# X-Track_Power.net
KiCad netlist of a schematic drawn in Altium Designer
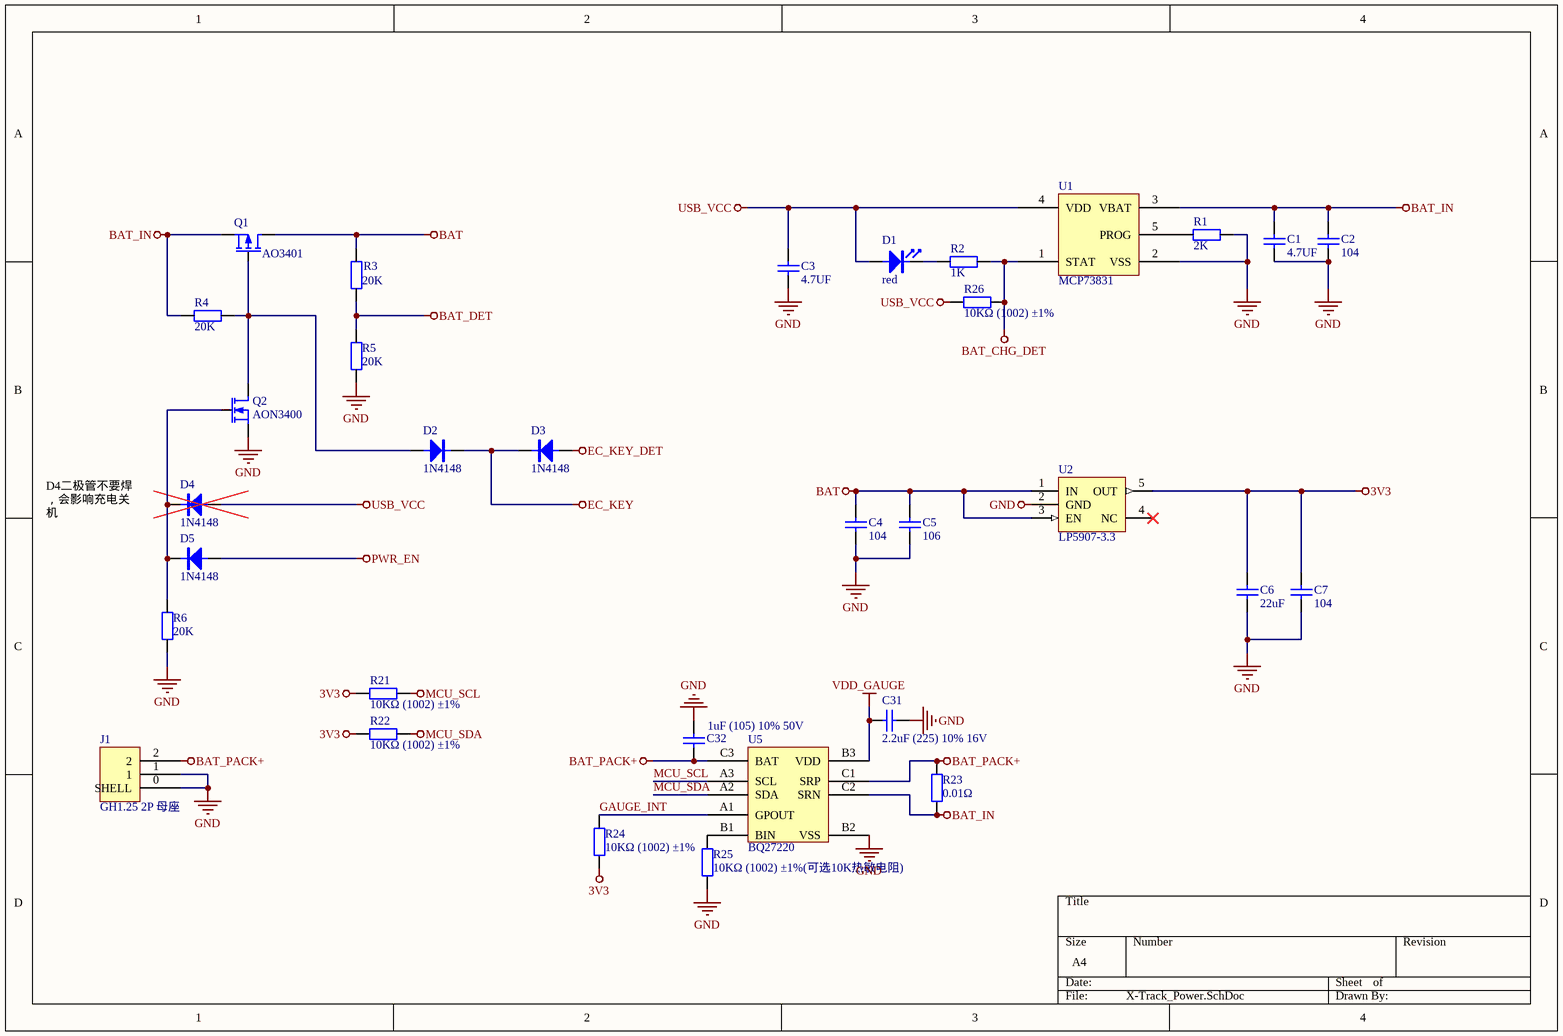
[diagram p0: X-Track_Power.SchDoc]

(export (version "E")
  (design (tool "Eeschema 10.0.6"))
  (components
    (comp (ref "C1")
      (value "4.7UF")
      (footprint "电容_C0805")
      (fields (field (name "C") "4.7UF"))
      (libsource (lib "元件库") (part "cap"))
    )
    (comp (ref "C2")
      (value "104")
      (footprint "电容_C0603")
      (fields (field (name "C") "104"))
      (libsource (lib "元件库") (part "cap"))
    )
    (comp (ref "C3")
      (value "4.7UF")
      (footprint "电容_C0805")
      (fields (field (name "C") "4.7UF"))
      (libsource (lib "元件库") (part "cap"))
    )
    (comp (ref "C4")
      (value "104")
      (footprint "电容_C0603")
      (fields (field (name "C") "104"))
      (libsource (lib "元件库") (part "cap"))
    )
    (comp (ref "C5")
      (value "106")
      (footprint "电容_C0603")
      (fields (field (name "C") "106"))
      (libsource (lib "元件库") (part "cap"))
    )
    (comp (ref "C6")
      (value "22uF")
      (footprint "电容_C1206")
      (fields (field (name "C") "22uF"))
      (libsource (lib "元件库") (part "cap"))
    )
    (comp (ref "C7")
      (value "104")
      (footprint "电容_C0603")
      (fields (field (name "C") "104"))
      (libsource (lib "元件库") (part "cap"))
    )
    (comp (ref "C31")
      (value "2.2uF (225) 10% 16V")
      (footprint "0603_C")
      (description "贴片电容")
      (libsource (lib "Cap") (part "0603 2.2uF (225) 10% 16V"))
    )
    (comp (ref "C32")
      (value "1uF (105) 10% 50V")
      (footprint "0603_C")
      (description "贴片电容")
      (libsource (lib "Cap") (part "0603 1uF (105) 10% 50V"))
    )
    (comp (ref "D1") (value "red") (footprint "LED_0603") (libsource (lib "元件库") (part "LED")))
    (comp (ref "D2")
      (value "1N4148")
      (footprint "二极管_SOD-323")
      (fields (field (name "_MODEL") "1N4148"))
      (libsource (lib "元件库") (part "Diode"))
    )
    (comp (ref "D3")
      (value "1N4148")
      (footprint "二极管_SOD-323")
      (fields (field (name "_MODEL") "1N4148"))
      (libsource (lib "元件库") (part "Diode"))
    )
    (comp (ref "D4")
      (value "1N4148")
      (footprint "二极管_SOD-323")
      (fields (field (name "_MODEL") "1N4148"))
      (libsource (lib "元件库") (part "Diode"))
    )
    (comp (ref "D5")
      (value "1N4148")
      (footprint "二极管_SOD-323")
      (fields (field (name "_MODEL") "1N4148"))
      (libsource (lib "元件库") (part "Diode"))
    )
    (comp (ref "J1")
      (value "GH1.25 2P 母座")
      (footprint "GH1.25 2P 母座")
      (libsource (lib "MyLibrary") (part "GH1.25 2P 母座"))
    )
    (comp (ref "Q1")
      (value "AO3401")
      (footprint "MOS_SOT-23")
      (fields (field (name "_MODEL") "AO3401"))
      (libsource (lib "元件库") (part "MOSFET-P"))
    )
    (comp (ref "Q2")
      (value "AON3400")
      (footprint "MOS_SOT-23")
      (fields (field (name "_MODEL") "AON3400"))
      (libsource (lib "元件库") (part "MOSFET-N"))
    )
    (comp (ref "R1")
      (value "2K")
      (footprint "电阻_R0603")
      (fields (field (name "R") "2K"))
      (libsource (lib "元件库") (part "Res"))
    )
    (comp (ref "R2")
      (value "1K")
      (footprint "电阻_R0603")
      (fields (field (name "R") "1K"))
      (libsource (lib "元件库") (part "Res"))
    )
    (comp (ref "R3")
      (value "20K")
      (footprint "电阻_R0603")
      (fields (field (name "R") "20K"))
      (libsource (lib "") (part "Res_3"))
    )
    (comp (ref "R4")
      (value "20K")
      (footprint "电阻_R0603")
      (fields (field (name "R") "20K"))
      (libsource (lib "") (part "Res_1"))
    )
    (comp (ref "R5")
      (value "20K")
      (footprint "电阻_R0603")
      (fields (field (name "R") "20K"))
      (libsource (lib "") (part "Res_3"))
    )
    (comp (ref "R6")
      (value "20K")
      (footprint "电阻_R0603")
      (fields (field (name "R") "20K"))
      (libsource (lib "") (part "Res_2"))
    )
    (comp (ref "R21")
      (value "10KΩ (1002) ±1%")
      (footprint "0603_R")
      (description "贴片电阻")
      (libsource (lib "RES") (part "0603 10KΩ (1002) 1%"))
    )
    (comp (ref "R22")
      (value "10KΩ (1002) ±1%")
      (footprint "0603_R")
      (description "贴片电阻")
      (libsource (lib "RES") (part "0603 10KΩ (1002) 1%"))
    )
    (comp (ref "R23")
      (value "0.01Ω")
      (footprint "0402_R")
      (description "贴片电阻")
      (libsource (lib "RES") (part "0402 49.9Ω (49R9) 1%"))
    )
    (comp (ref "R24")
      (value "10KΩ (1002) ±1%")
      (footprint "0603_R")
      (description "贴片电阻")
      (libsource (lib "") (part "0603 10KΩ (1002) 1%_1"))
    )
    (comp (ref "R25")
      (value "10KΩ (1002) ±1%(可选10K热敏电阻)")
      (footprint "0603_R")
      (description "贴片电阻")
      (libsource (lib "") (part "0603 10KΩ (1002) 1%_1"))
    )
    (comp (ref "R26")
      (value "10KΩ (1002) ±1%")
      (footprint "0603_R")
      (description "贴片电阻")
      (libsource (lib "RES") (part "0603 10KΩ (1002) 1%"))
    )
    (comp (ref "U1")
      (value "MCP73831")
      (footprint "SOT23-5")
      (description "线性充电管理控制器")
      (libsource (lib "TriggersLib") (part "MCP73831"))
    )
    (comp (ref "U2")
      (value "LP5907-3.3")
      (footprint "SOT23-5")
      (description "LDO")
      (libsource (lib "WatchX_TEST") (part "LP5907"))
    )
    (comp (ref "U5") (value "BQ27220") (footprint "BQ27220") (libsource (lib "MyLibrary") (part "BQ27220")))
  )
  (nets
    (net (code "1") (name "/GAUGE_INT") (class "Default")
      (node (ref "R24") (pin "2") (pinfunction "2_2") (pintype "passive"))
      (node (ref "U5") (pin "A1") (pinfunction "GPOUT_A1") (pintype "passive"))
    )
    (net (code "2") (name "3V3") (class "Default")
      (node (ref "C6") (pin "2") (pinfunction "2_2") (pintype "passive"))
      (node (ref "C7") (pin "2") (pinfunction "2_2") (pintype "passive"))
      (node (ref "R21") (pin "2") (pinfunction "2_2") (pintype "passive"))
      (node (ref "R22") (pin "2") (pinfunction "2_2") (pintype "passive"))
      (node (ref "R24") (pin "1") (pinfunction "1_1") (pintype "passive"))
      (node (ref "U2") (pin "5") (pinfunction "OUT_5") (pintype "output"))
    )
    (net (code "3") (name "BAT") (class "Default")
      (node (ref "C4") (pin "2") (pinfunction "2_2") (pintype "passive"))
      (node (ref "C5") (pin "2") (pinfunction "2_2") (pintype "passive"))
      (node (ref "Q1") (pin "2") (pinfunction "D_2") (pintype "passive"))
      (node (ref "R3") (pin "2") (pinfunction "2_2") (pintype "passive"))
      (node (ref "U2") (pin "1") (pinfunction "IN_1") (pintype "power_in"))
      (node (ref "U2") (pin "3") (pinfunction "EN_3") (pintype "input"))
    )
    (net (code "4") (name "BAT_CHG_DET") (class "Default")
      (node (ref "R2") (pin "1") (pinfunction "1_1") (pintype "passive"))
      (node (ref "R26") (pin "1") (pinfunction "1_1") (pintype "passive"))
      (node (ref "U1") (pin "1") (pinfunction "STAT_1") (pintype "passive"))
    )
    (net (code "5") (name "BAT_DET") (class "Default")
      (node (ref "R3") (pin "1") (pinfunction "1_1") (pintype "passive"))
      (node (ref "R5") (pin "2") (pinfunction "2_2") (pintype "passive"))
    )
    (net (code "6") (name "BAT_IN") (class "Default")
      (node (ref "C1") (pin "2") (pinfunction "2_2") (pintype "passive"))
      (node (ref "C2") (pin "1") (pinfunction "1_1") (pintype "passive"))
      (node (ref "Q1") (pin "3") (pinfunction "S_3") (pintype "passive"))
      (node (ref "R23") (pin "1") (pinfunction "1_1") (pintype "passive"))
      (node (ref "R4") (pin "1") (pinfunction "1_1") (pintype "passive"))
      (node (ref "U1") (pin "3") (pinfunction "VBAT_3") (pintype "passive"))
      (node (ref "U5") (pin "C2") (pinfunction "SRN_C2") (pintype "passive"))
    )
    (net (code "7") (name "BAT_PACK+") (class "Default")
      (node (ref "C32") (pin "2") (pinfunction "2_2") (pintype "passive"))
      (node (ref "J1") (pin "2") (pinfunction "2_2") (pintype "passive"))
      (node (ref "R23") (pin "2") (pinfunction "2_2") (pintype "passive"))
      (node (ref "U5") (pin "C1") (pinfunction "SRP_C1") (pintype "passive"))
      (node (ref "U5") (pin "C3") (pinfunction "BAT_C3") (pintype "passive"))
    )
    (net (code "8") (name "EC_KEY") (class "Default")
      (node (ref "D2") (pin "K") (pinfunction "K_K") (pintype "passive"))
      (node (ref "D3") (pin "K") (pinfunction "K_K") (pintype "passive"))
    )
    (net (code "9") (name "EC_KEY_DET") (class "Default")
      (node (ref "D3") (pin "A") (pinfunction "A_A") (pintype "passive"))
    )
    (net (code "10") (name "GND") (class "Default")
      (node (ref "C1") (pin "1") (pinfunction "1_1") (pintype "passive"))
      (node (ref "C2") (pin "2") (pinfunction "2_2") (pintype "passive"))
      (node (ref "C3") (pin "1") (pinfunction "1_1") (pintype "passive"))
      (node (ref "C31") (pin "2") (pinfunction "2_2") (pintype "passive"))
      (node (ref "C32") (pin "1") (pinfunction "1_1") (pintype "passive"))
      (node (ref "C4") (pin "1") (pinfunction "1_1") (pintype "passive"))
      (node (ref "C5") (pin "1") (pinfunction "1_1") (pintype "passive"))
      (node (ref "C6") (pin "1") (pinfunction "1_1") (pintype "passive"))
      (node (ref "C7") (pin "1") (pinfunction "1_1") (pintype "passive"))
      (node (ref "J1") (pin "0") (pinfunction "SHELL_0") (pintype "passive"))
      (node (ref "J1") (pin "1") (pinfunction "1_1") (pintype "passive"))
      (node (ref "Q2") (pin "3") (pinfunction "S_3") (pintype "passive"))
      (node (ref "R1") (pin "1") (pinfunction "1_1") (pintype "passive"))
      (node (ref "R25") (pin "1") (pinfunction "1_1") (pintype "passive"))
      (node (ref "R5") (pin "1") (pinfunction "1_1") (pintype "passive"))
      (node (ref "R6") (pin "2") (pinfunction "2_2") (pintype "passive"))
      (node (ref "U1") (pin "2") (pinfunction "VSS_2") (pintype "passive"))
      (node (ref "U2") (pin "2") (pinfunction "GND_2") (pintype "passive"))
      (node (ref "U5") (pin "B2") (pinfunction "VSS_B2") (pintype "passive"))
    )
    (net (code "11") (name "MCU_SCL") (class "Default")
      (node (ref "R21") (pin "1") (pinfunction "1_1") (pintype "passive"))
      (node (ref "U5") (pin "A3") (pinfunction "SCL_A3") (pintype "passive"))
    )
    (net (code "12") (name "MCU_SDA") (class "Default")
      (node (ref "R22") (pin "1") (pinfunction "1_1") (pintype "passive"))
      (node (ref "U5") (pin "A2") (pinfunction "SDA_A2") (pintype "passive"))
    )
    (net (code "13") (name "Net-(D1-PadK)") (class "Default")
      (node (ref "D1") (pin "K") (pinfunction "K_K") (pintype "passive"))
      (node (ref "R2") (pin "2") (pinfunction "2_2") (pintype "passive"))
    )
    (net (code "14") (name "Net-(Q1-G)") (class "Default")
      (node (ref "D2") (pin "A") (pinfunction "A_A") (pintype "passive"))
      (node (ref "Q1") (pin "1") (pinfunction "G_1") (pintype "passive"))
      (node (ref "Q2") (pin "2") (pinfunction "D_2") (pintype "passive"))
      (node (ref "R4") (pin "2") (pinfunction "2_2") (pintype "passive"))
    )
    (net (code "15") (name "Net-(Q2-G)") (class "Default")
      (node (ref "D4") (pin "K") (pinfunction "K_K") (pintype "passive"))
      (node (ref "D5") (pin "K") (pinfunction "K_K") (pintype "passive"))
      (node (ref "Q2") (pin "1") (pinfunction "G_1") (pintype "passive"))
      (node (ref "R6") (pin "1") (pinfunction "1_1") (pintype "passive"))
    )
    (net (code "16") (name "Net-(U1-PROG)") (class "Default")
      (node (ref "R1") (pin "2") (pinfunction "2_2") (pintype "passive"))
      (node (ref "U1") (pin "5") (pinfunction "PROG_5") (pintype "passive"))
    )
    (net (code "17") (name "Net-(U5-BIN)") (class "Default")
      (node (ref "R25") (pin "2") (pinfunction "2_2") (pintype "passive"))
      (node (ref "U5") (pin "B1") (pinfunction "BIN_B1") (pintype "passive"))
    )
    (net (code "18") (name "PWR_EN") (class "Default")
      (node (ref "D5") (pin "A") (pinfunction "A_A") (pintype "passive"))
    )
    (net (code "19") (name "USB_VCC") (class "Default")
      (node (ref "C3") (pin "2") (pinfunction "2_2") (pintype "passive"))
      (node (ref "D1") (pin "A") (pinfunction "A_A") (pintype "passive"))
      (node (ref "D4") (pin "A") (pinfunction "A_A") (pintype "passive"))
      (node (ref "R26") (pin "2") (pinfunction "2_2") (pintype "passive"))
      (node (ref "U1") (pin "4") (pinfunction "VDD_4") (pintype "passive"))
    )
    (net (code "20") (name "VDD_GAUGE") (class "Default")
      (node (ref "C31") (pin "1") (pinfunction "1_1") (pintype "passive"))
      (node (ref "U5") (pin "B3") (pinfunction "VDD_B3") (pintype "passive"))
    )
    (net (code "21") (name "unconnected-(U2-NC-Pad4)") (class "Default")
      (node (ref "U2") (pin "4") (pinfunction "NC_4") (pintype "passive+no_connect"))
    )
  )
)
